# HITB_AMS_V1_3.net
KiCad netlist of a schematic drawn in EAGLE
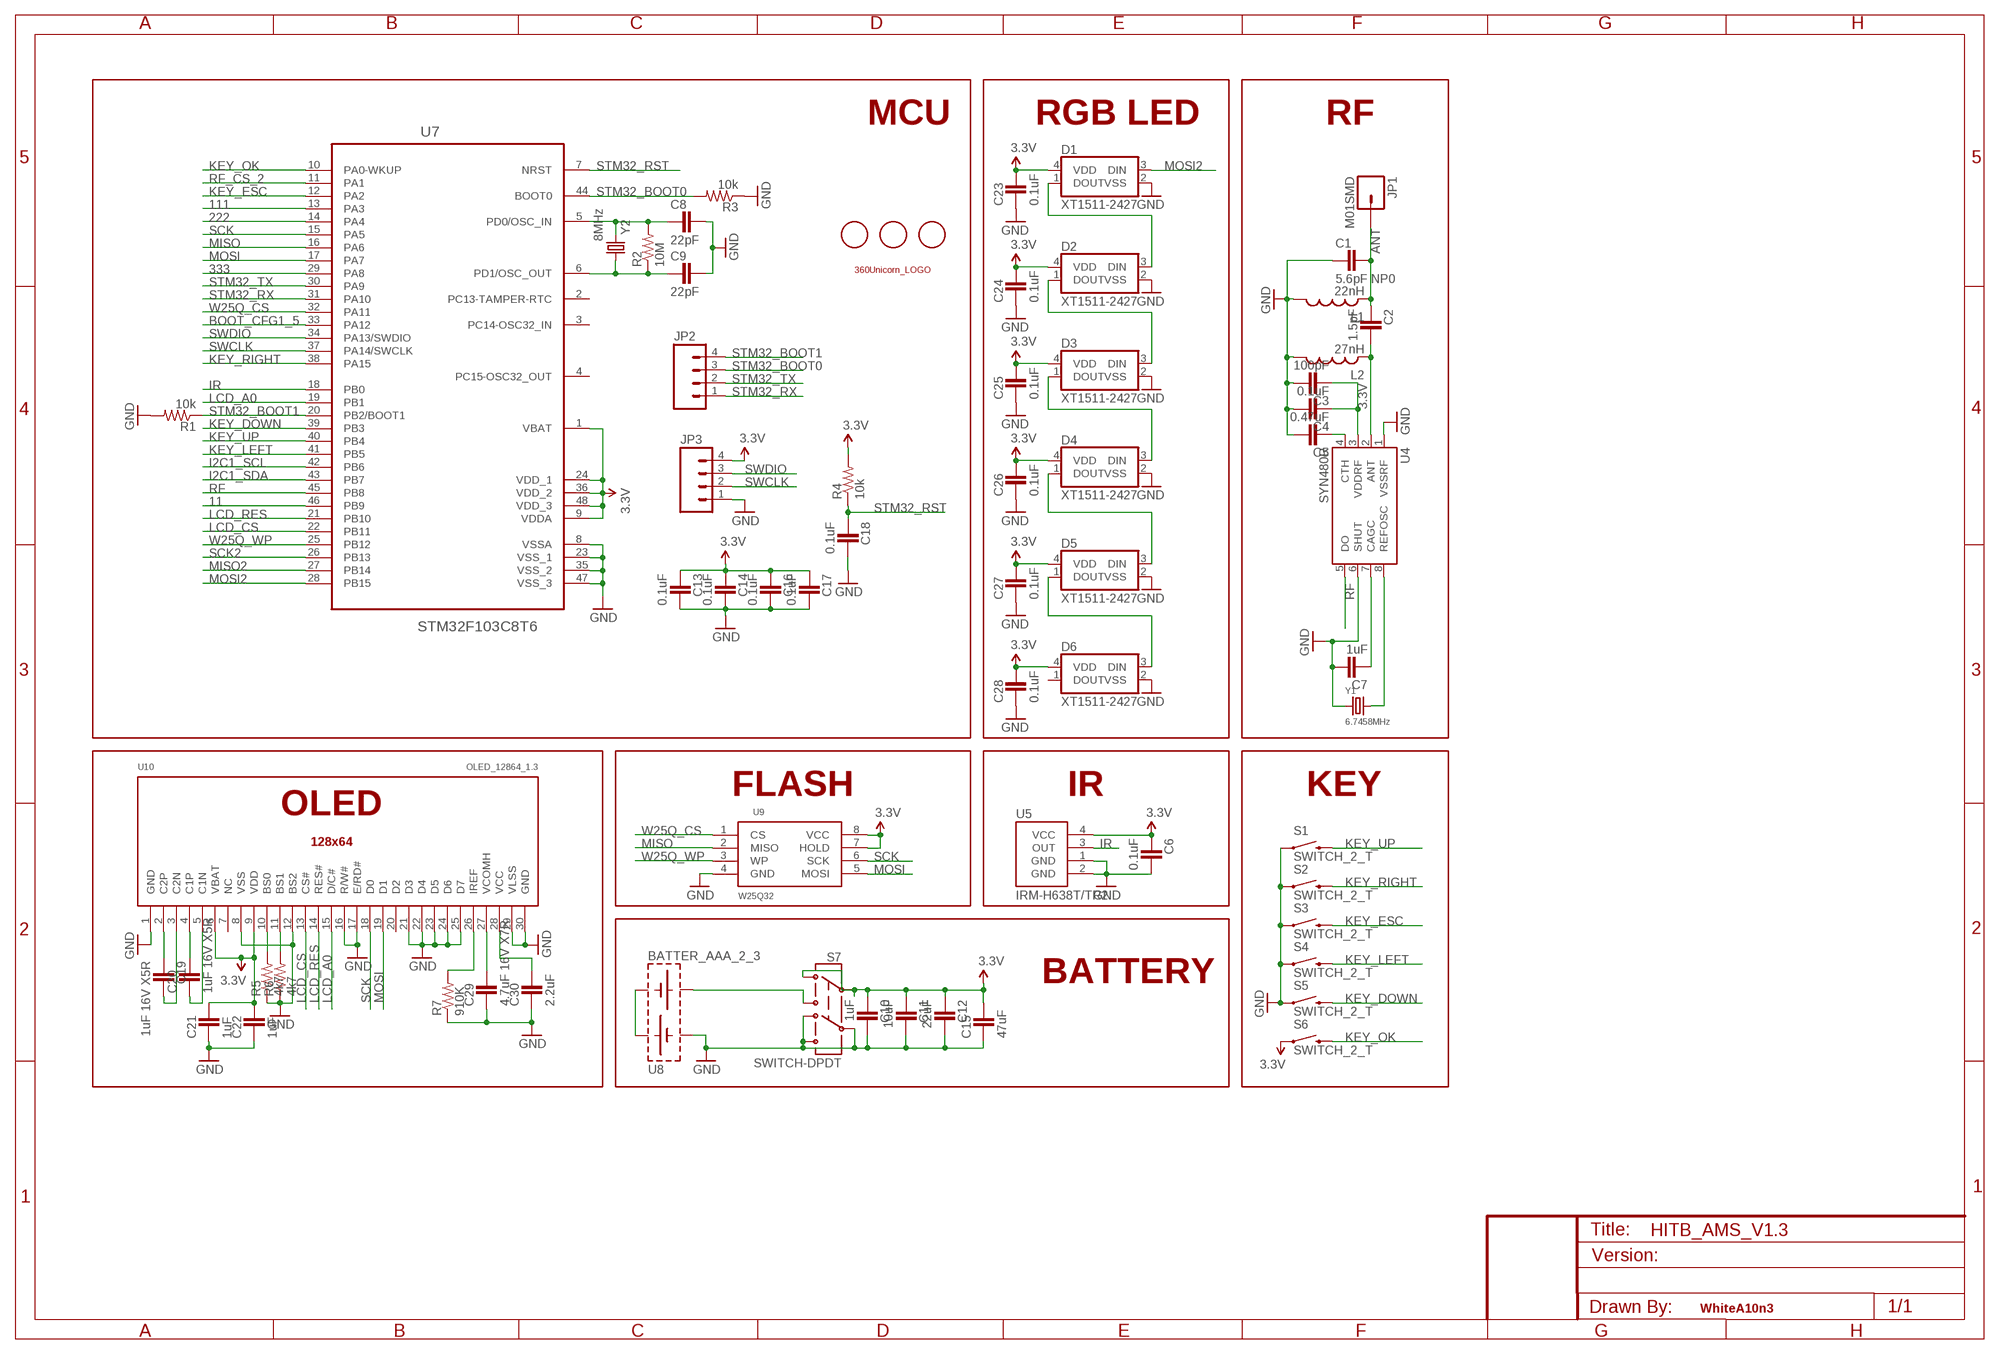
[diagram p0: schematic, sheet 1]

(export (version "E")
  (design (tool "Eeschema 10.0.6"))
  (components
    (comp (ref "C1")
      (value "5.6pF NP0")
      (footprint "eagle-import:0603-CAP")
      (libsource (lib "eagle-import") (part "CAP0603"))
    )
    (comp (ref "C2")
      (value "1.5pF")
      (footprint "eagle-import:0603-CAP")
      (libsource (lib "eagle-import") (part "CAP0603"))
    )
    (comp (ref "C3")
      (value "100pF")
      (footprint "eagle-import:0603-CAP")
      (libsource (lib "eagle-import") (part "CAP0603"))
    )
    (comp (ref "C4")
      (value "0.1uF")
      (footprint "eagle-import:0603-CAP")
      (libsource (lib "eagle-import") (part "CAP0603"))
    )
    (comp (ref "C5")
      (value "0.47uF")
      (footprint "eagle-import:0603-CAP")
      (libsource (lib "eagle-import") (part "CAP0603"))
    )
    (comp (ref "C6")
      (value "0.1uF")
      (footprint "eagle-import:0603-CAP")
      (libsource (lib "eagle-import") (part "CAP0603"))
    )
    (comp (ref "C7")
      (value "1uF")
      (footprint "eagle-import:0603-CAP")
      (libsource (lib "eagle-import") (part "CAP0603"))
    )
    (comp (ref "C8")
      (value "22pF")
      (footprint "eagle-import:0603-CAP")
      (libsource (lib "eagle-import") (part "CAP0603"))
    )
    (comp (ref "C9")
      (value "22pF")
      (footprint "eagle-import:0603-CAP")
      (libsource (lib "eagle-import") (part "CAP0603"))
    )
    (comp (ref "C10")
      (value "1uF")
      (footprint "eagle-import:0603-CAP")
      (libsource (lib "eagle-import") (part "CAP0603"))
    )
    (comp (ref "C11")
      (value "10uF")
      (footprint "eagle-import:0603-CAP")
      (libsource (lib "eagle-import") (part "CAP0603"))
    )
    (comp (ref "C12")
      (value "22uF")
      (footprint "eagle-import:0603-CAP")
      (libsource (lib "eagle-import") (part "CAP0603"))
    )
    (comp (ref "C13")
      (value "0.1uF")
      (footprint "eagle-import:0603-CAP")
      (libsource (lib "eagle-import") (part "CAP0603"))
    )
    (comp (ref "C14")
      (value "0.1uF")
      (footprint "eagle-import:0603-CAP")
      (libsource (lib "eagle-import") (part "CAP0603"))
    )
    (comp (ref "C15")
      (value "47uF")
      (footprint "eagle-import:1206")
      (libsource (lib "eagle-import") (part "CAP1206"))
    )
    (comp (ref "C16")
      (value "0.1uF")
      (footprint "eagle-import:0603-CAP")
      (libsource (lib "eagle-import") (part "CAP0603"))
    )
    (comp (ref "C17")
      (value "0.1uF")
      (footprint "eagle-import:0603-CAP")
      (libsource (lib "eagle-import") (part "CAP0603"))
    )
    (comp (ref "C18")
      (value "0.1uF")
      (footprint "eagle-import:0603-CAP")
      (libsource (lib "eagle-import") (part "CAP0603"))
    )
    (comp (ref "C19")
      (value "1uF 16V X5R")
      (footprint "eagle-import:0603-CAP")
      (libsource (lib "eagle-import") (part "CAP0603"))
    )
    (comp (ref "C20")
      (value "1uF 16V X5R")
      (footprint "eagle-import:0603-CAP")
      (libsource (lib "eagle-import") (part "CAP0603"))
    )
    (comp (ref "C21")
      (value "1uF")
      (footprint "eagle-import:0603-CAP")
      (libsource (lib "eagle-import") (part "CAP0603"))
    )
    (comp (ref "C22")
      (value "1uF")
      (footprint "eagle-import:0603-CAP")
      (libsource (lib "eagle-import") (part "CAP0603"))
    )
    (comp (ref "C23")
      (value "0.1uF")
      (footprint "eagle-import:0603-CAP")
      (libsource (lib "eagle-import") (part "CAP0603"))
    )
    (comp (ref "C24")
      (value "0.1uF")
      (footprint "eagle-import:0603-CAP")
      (libsource (lib "eagle-import") (part "CAP0603"))
    )
    (comp (ref "C25")
      (value "0.1uF")
      (footprint "eagle-import:0603-CAP")
      (libsource (lib "eagle-import") (part "CAP0603"))
    )
    (comp (ref "C26")
      (value "0.1uF")
      (footprint "eagle-import:0603-CAP")
      (libsource (lib "eagle-import") (part "CAP0603"))
    )
    (comp (ref "C27")
      (value "0.1uF")
      (footprint "eagle-import:0603-CAP")
      (libsource (lib "eagle-import") (part "CAP0603"))
    )
    (comp (ref "C28")
      (value "0.1uF")
      (footprint "eagle-import:0603-CAP")
      (libsource (lib "eagle-import") (part "CAP0603"))
    )
    (comp (ref "C29")
      (value "4.7uF 16V X7R")
      (footprint "eagle-import:0603-CAP")
      (libsource (lib "eagle-import") (part "CAP0603"))
    )
    (comp (ref "C30")
      (value "2.2uF")
      (footprint "eagle-import:0603-CAP")
      (libsource (lib "eagle-import") (part "CAP0603"))
    )
    (comp (ref "D1")
      (value "XT1511-2427")
      (footprint "eagle-import:RGB_2427")
      (libsource (lib "eagle-import") (part "XT1511-2427"))
    )
    (comp (ref "D2")
      (value "XT1511-2427")
      (footprint "eagle-import:RGB_2427")
      (libsource (lib "eagle-import") (part "XT1511-2427"))
    )
    (comp (ref "D3")
      (value "XT1511-2427")
      (footprint "eagle-import:RGB_2427")
      (libsource (lib "eagle-import") (part "XT1511-2427"))
    )
    (comp (ref "D4")
      (value "XT1511-2427")
      (footprint "eagle-import:RGB_2427")
      (libsource (lib "eagle-import") (part "XT1511-2427"))
    )
    (comp (ref "D5")
      (value "XT1511-2427")
      (footprint "eagle-import:RGB_2427")
      (libsource (lib "eagle-import") (part "XT1511-2427"))
    )
    (comp (ref "D6")
      (value "XT1511-2427")
      (footprint "eagle-import:RGB_2427")
      (libsource (lib "eagle-import") (part "XT1511-2427"))
    )
    (comp (ref "JP1")
      (value "M01SMD")
      (footprint "eagle-import:LUXEON-PAD")
      (libsource (lib "eagle-import") (part "M01SMD"))
    )
    (comp (ref "JP2")
      (value "M04_TEST_2")
      (footprint "eagle-import:1X04_TEST_2")
      (libsource (lib "eagle-import") (part "M04_TEST_2"))
    )
    (comp (ref "JP3")
      (value "M04_TEST_2")
      (footprint "eagle-import:1X04_TEST_2")
      (libsource (lib "eagle-import") (part "M04_TEST_2"))
    )
    (comp (ref "L1")
      (value "22nH")
      (footprint "eagle-import:0603")
      (libsource (lib "eagle-import") (part "INDUCTOR0603"))
    )
    (comp (ref "L2")
      (value "27nH")
      (footprint "eagle-import:0603")
      (libsource (lib "eagle-import") (part "INDUCTOR0603"))
    )
    (comp (ref "R1")
      (value "10k")
      (footprint "eagle-import:0603-RES")
      (libsource (lib "eagle-import") (part "RESISTOR0603-RES"))
    )
    (comp (ref "R2")
      (value "10M")
      (footprint "eagle-import:0603-RES")
      (libsource (lib "eagle-import") (part "RESISTOR0603-RES"))
    )
    (comp (ref "R3")
      (value "10k")
      (footprint "eagle-import:0603-RES")
      (libsource (lib "eagle-import") (part "RESISTOR0603-RES"))
    )
    (comp (ref "R4")
      (value "10k")
      (footprint "eagle-import:0603-RES")
      (libsource (lib "eagle-import") (part "RESISTOR0603-RES"))
    )
    (comp (ref "R5")
      (value "4k7")
      (footprint "eagle-import:0603-RES")
      (libsource (lib "eagle-import") (part "RESISTOR0603-RES"))
    )
    (comp (ref "R6")
      (value "4k7")
      (footprint "eagle-import:0603-RES")
      (libsource (lib "eagle-import") (part "RESISTOR0603-RES"))
    )
    (comp (ref "R7")
      (value "910K")
      (footprint "eagle-import:0603-RES")
      (libsource (lib "eagle-import") (part "RESISTOR0603-RES"))
    )
    (comp (ref "S1")
      (value "SWITCH_2_T")
      (footprint "eagle-import:BUTTON_TSSURX")
      (libsource (lib "eagle-import") (part "SWITCH_2_T"))
    )
    (comp (ref "S2")
      (value "SWITCH_2_T")
      (footprint "eagle-import:BUTTON_TSSURX")
      (libsource (lib "eagle-import") (part "SWITCH_2_T"))
    )
    (comp (ref "S3")
      (value "SWITCH_2_T")
      (footprint "eagle-import:BUTTON_TSSURX")
      (libsource (lib "eagle-import") (part "SWITCH_2_T"))
    )
    (comp (ref "S4")
      (value "SWITCH_2_T")
      (footprint "eagle-import:BUTTON_TSSURX")
      (libsource (lib "eagle-import") (part "SWITCH_2_T"))
    )
    (comp (ref "S5")
      (value "SWITCH_2_T")
      (footprint "eagle-import:BUTTON_TSSURX")
      (libsource (lib "eagle-import") (part "SWITCH_2_T"))
    )
    (comp (ref "S6")
      (value "SWITCH_2_T")
      (footprint "eagle-import:BUTTON_TSSURX")
      (libsource (lib "eagle-import") (part "SWITCH_2_T"))
    )
    (comp (ref "S7")
      (value "SWITCH-DPDT")
      (footprint "eagle-import:MSS22D18")
      (libsource (lib "eagle-import") (part "SWITCH-DPDT"))
    )
    (comp (ref "U1")
      (value "FIDUCIALMOUNT")
      (footprint "eagle-import:FIDUCIA-MOUNT")
      (libsource (lib "eagle-import") (part "FIDUCIALMOUNT"))
    )
    (comp (ref "U2")
      (value "FIDUCIALMOUNT")
      (footprint "eagle-import:FIDUCIA-MOUNT")
      (libsource (lib "eagle-import") (part "FIDUCIALMOUNT"))
    )
    (comp (ref "U3")
      (value "FIDUCIALMOUNT")
      (footprint "eagle-import:FIDUCIA-MOUNT")
      (libsource (lib "eagle-import") (part "FIDUCIALMOUNT"))
    )
    (comp (ref "U4")
      (value "SYN480R")
      (footprint "eagle-import:SO08")
      (libsource (lib "eagle-import") (part "SYN480R"))
    )
    (comp (ref "U5")
      (value "IRM-H638T/TR2")
      (footprint "eagle-import:IR_RECEIVE")
      (libsource (lib "eagle-import") (part "IR_RECIVE"))
    )
    (comp (ref "U6")
      (value "360UNICORN_LOGO_0.8_STOP")
      (footprint "eagle-import:360UNICORN_S0.8")
      (libsource (lib "eagle-import") (part "360UNICORN_LOGO_0.8_STOP"))
    )
    (comp (ref "U7")
      (value "STM32F103C8T6")
      (footprint "eagle-import:TQFP48")
      (libsource (lib "eagle-import") (part "STM32F103C8T6"))
    )
    (comp (ref "U8")
      (value "BATTER_AAA_2_3")
      (footprint "eagle-import:BATTER_AAA_3")
      (libsource (lib "eagle-import") (part "BATTER_AAA_2_3"))
    )
    (comp (ref "U9")
      (value "W25Q32")
      (footprint "eagle-import:SO08-EIAJ")
      (libsource (lib "eagle-import") (part "SPI_FLASH-X25XXSMD1"))
    )
    (comp (ref "U10")
      (value "OLED_12864_1.3")
      (footprint "eagle-import:OLED_12864_1.3")
      (libsource (lib "eagle-import") (part "OLED_12864_1.3"))
    )
    (comp (ref "Y1")
      (value "6.7458MHz")
      (footprint "eagle-import:HC49UP")
      (libsource (lib "eagle-import") (part "CRYSTALSMD"))
    )
    (comp (ref "Y2")
      (value "8MHz")
      (footprint "eagle-import:CRYSTAL-SMD-3225")
      (libsource (lib "eagle-import") (part "CRYSTAL_3225"))
    )
  )
  (nets
    (net (code "1") (name "/11") (class "Default")
      (node (ref "U7") (pin "46") (pinfunction "PB9_46") (pintype "bidirectional"))
    )
    (net (code "2") (name "/111") (class "Default")
      (node (ref "U7") (pin "13") (pinfunction "PA3_13") (pintype "bidirectional"))
    )
    (net (code "3") (name "/222") (class "Default")
      (node (ref "U7") (pin "14") (pinfunction "PA4_14") (pintype "bidirectional"))
    )
    (net (code "4") (name "/333") (class "Default")
      (node (ref "U7") (pin "29") (pinfunction "PA8_29") (pintype "bidirectional"))
    )
    (net (code "5") (name "/ANT") (class "Default")
      (node (ref "C1") (pin "1") (pinfunction "1_1") (pintype "passive"))
      (node (ref "C2") (pin "2") (pinfunction "2_2") (pintype "passive"))
      (node (ref "JP1") (pin "P$1") (pinfunction "1_P$1") (pintype "passive"))
      (node (ref "L1") (pin "1") (pinfunction "1_1") (pintype "passive"))
    )
    (net (code "6") (name "/BOOT_CFG1_5") (class "Default")
      (node (ref "U7") (pin "33") (pinfunction "PA12_33") (pintype "bidirectional"))
    )
    (net (code "7") (name "/I2C1_SCL") (class "Default")
      (node (ref "U7") (pin "42") (pinfunction "PB6_42") (pintype "bidirectional"))
    )
    (net (code "8") (name "/I2C1_SDA") (class "Default")
      (node (ref "U7") (pin "43") (pinfunction "PB7_43") (pintype "bidirectional"))
    )
    (net (code "9") (name "/IR") (class "Default")
      (node (ref "U5") (pin "3") (pinfunction "OUT_3") (pintype "bidirectional"))
      (node (ref "U7") (pin "18") (pinfunction "PB0_18") (pintype "bidirectional"))
    )
    (net (code "10") (name "/KEY_DOWN") (class "Default")
      (node (ref "S5") (pin "P$2") (pinfunction "2_P$2") (pintype "passive"))
      (node (ref "U7") (pin "39") (pinfunction "PB3_39") (pintype "bidirectional"))
    )
    (net (code "11") (name "/KEY_ESC") (class "Default")
      (node (ref "S3") (pin "P$2") (pinfunction "2_P$2") (pintype "passive"))
      (node (ref "U7") (pin "12") (pinfunction "PA2_12") (pintype "bidirectional"))
    )
    (net (code "12") (name "/KEY_LEFT") (class "Default")
      (node (ref "S4") (pin "P$2") (pinfunction "2_P$2") (pintype "passive"))
      (node (ref "U7") (pin "41") (pinfunction "PB5_41") (pintype "bidirectional"))
    )
    (net (code "13") (name "/KEY_OK") (class "Default")
      (node (ref "S6") (pin "P$2") (pinfunction "2_P$2") (pintype "passive"))
      (node (ref "U7") (pin "10") (pinfunction "PA0-WKUP_10") (pintype "bidirectional"))
    )
    (net (code "14") (name "/KEY_RIGHT") (class "Default")
      (node (ref "S2") (pin "P$2") (pinfunction "2_P$2") (pintype "passive"))
      (node (ref "U7") (pin "38") (pinfunction "PA15_38") (pintype "bidirectional"))
    )
    (net (code "15") (name "/KEY_UP") (class "Default")
      (node (ref "S1") (pin "P$2") (pinfunction "2_P$2") (pintype "passive"))
      (node (ref "U7") (pin "40") (pinfunction "PB4_40") (pintype "bidirectional"))
    )
    (net (code "16") (name "/LCD_A0") (class "Default")
      (node (ref "U10") (pin "15") (pinfunction "D/C#_15") (pintype "bidirectional"))
      (node (ref "U7") (pin "19") (pinfunction "PB1_19") (pintype "bidirectional"))
    )
    (net (code "17") (name "/LCD_CS") (class "Default")
      (node (ref "U10") (pin "13") (pinfunction "CS#_13") (pintype "bidirectional"))
      (node (ref "U7") (pin "22") (pinfunction "PB11_22") (pintype "bidirectional"))
    )
    (net (code "18") (name "/LCD_RES") (class "Default")
      (node (ref "U10") (pin "14") (pinfunction "RES#_14") (pintype "bidirectional"))
      (node (ref "U7") (pin "21") (pinfunction "PB10_21") (pintype "bidirectional"))
    )
    (net (code "19") (name "/MISO") (class "Default")
      (node (ref "U7") (pin "16") (pinfunction "PA6_16") (pintype "bidirectional"))
      (node (ref "U9") (pin "2") (pinfunction "MISO_2") (pintype "bidirectional"))
    )
    (net (code "20") (name "/MISO2") (class "Default")
      (node (ref "U7") (pin "27") (pinfunction "PB14_27") (pintype "bidirectional"))
    )
    (net (code "21") (name "/MOSI") (class "Default")
      (node (ref "U10") (pin "19") (pinfunction "D1_19") (pintype "bidirectional"))
      (node (ref "U7") (pin "17") (pinfunction "PA7_17") (pintype "bidirectional"))
      (node (ref "U9") (pin "5") (pinfunction "MOSI_5") (pintype "bidirectional"))
    )
    (net (code "22") (name "/MOSI2") (class "Default")
      (node (ref "D1") (pin "3") (pinfunction "DIN_3") (pintype "bidirectional"))
      (node (ref "U7") (pin "28") (pinfunction "PB15_28") (pintype "bidirectional"))
    )
    (net (code "23") (name "/RF") (class "Default")
      (node (ref "U4") (pin "5") (pinfunction "DO_5") (pintype "bidirectional"))
      (node (ref "U7") (pin "45") (pinfunction "PB8_45") (pintype "bidirectional"))
    )
    (net (code "24") (name "/RF_CS_2") (class "Default")
      (node (ref "U7") (pin "11") (pinfunction "PA1_11") (pintype "bidirectional"))
    )
    (net (code "25") (name "/SCK") (class "Default")
      (node (ref "U10") (pin "18") (pinfunction "D0_18") (pintype "bidirectional"))
      (node (ref "U7") (pin "15") (pinfunction "PA5_15") (pintype "bidirectional"))
      (node (ref "U9") (pin "6") (pinfunction "SCK_6") (pintype "bidirectional"))
    )
    (net (code "26") (name "/SCK2") (class "Default")
      (node (ref "U7") (pin "26") (pinfunction "PB13_26") (pintype "bidirectional"))
    )
    (net (code "27") (name "/STM32_BOOT0") (class "Default")
      (node (ref "JP2") (pin "3") (pinfunction "3_3") (pintype "passive"))
      (node (ref "R3") (pin "2") (pinfunction "2_2") (pintype "passive"))
      (node (ref "U7") (pin "44") (pinfunction "BOOT0_44") (pintype "input"))
    )
    (net (code "28") (name "/STM32_BOOT1") (class "Default")
      (node (ref "JP2") (pin "4") (pinfunction "4_4") (pintype "passive"))
      (node (ref "R1") (pin "1") (pinfunction "1_1") (pintype "passive"))
      (node (ref "U7") (pin "20") (pinfunction "PB2/BOOT1_20") (pintype "bidirectional"))
    )
    (net (code "29") (name "/STM32_RST") (class "Default")
      (node (ref "C18") (pin "2") (pinfunction "2_2") (pintype "passive"))
      (node (ref "R4") (pin "1") (pinfunction "1_1") (pintype "passive"))
      (node (ref "U7") (pin "7") (pinfunction "NRST_7") (pintype "bidirectional"))
    )
    (net (code "30") (name "/STM32_RX") (class "Default")
      (node (ref "JP2") (pin "1") (pinfunction "1_1") (pintype "passive"))
      (node (ref "U7") (pin "31") (pinfunction "PA10_31") (pintype "bidirectional"))
    )
    (net (code "31") (name "/STM32_TX") (class "Default")
      (node (ref "JP2") (pin "2") (pinfunction "2_2") (pintype "passive"))
      (node (ref "U7") (pin "30") (pinfunction "PA9_30") (pintype "bidirectional"))
    )
    (net (code "32") (name "/SWCLK") (class "Default")
      (node (ref "JP3") (pin "2") (pinfunction "2_2") (pintype "passive"))
      (node (ref "U7") (pin "37") (pinfunction "PA14/SWCLK_37") (pintype "bidirectional"))
    )
    (net (code "33") (name "/SWDIO") (class "Default")
      (node (ref "JP3") (pin "3") (pinfunction "3_3") (pintype "passive"))
      (node (ref "U7") (pin "34") (pinfunction "PA13/SWDIO_34") (pintype "bidirectional"))
    )
    (net (code "34") (name "/W25Q_CS") (class "Default")
      (node (ref "U7") (pin "32") (pinfunction "PA11_32") (pintype "bidirectional"))
      (node (ref "U9") (pin "1") (pinfunction "CS_1") (pintype "bidirectional"))
    )
    (net (code "35") (name "/W25Q_WP") (class "Default")
      (node (ref "U7") (pin "25") (pinfunction "PB12_25") (pintype "bidirectional"))
      (node (ref "U9") (pin "3") (pinfunction "WP_3") (pintype "bidirectional"))
    )
    (net (code "36") (name "3.3V") (class "Default")
      (node (ref "C10") (pin "2") (pinfunction "2_2") (pintype "passive"))
      (node (ref "C11") (pin "2") (pinfunction "2_2") (pintype "passive"))
      (node (ref "C12") (pin "2") (pinfunction "2_2") (pintype "passive"))
      (node (ref "C13") (pin "2") (pinfunction "2_2") (pintype "passive"))
      (node (ref "C14") (pin "2") (pinfunction "2_2") (pintype "passive"))
      (node (ref "C15") (pin "1") (pinfunction "1_1") (pintype "passive"))
      (node (ref "C16") (pin "2") (pinfunction "2_2") (pintype "passive"))
      (node (ref "C17") (pin "2") (pinfunction "2_2") (pintype "passive"))
      (node (ref "C21") (pin "1") (pinfunction "1_1") (pintype "passive"))
      (node (ref "C22") (pin "1") (pinfunction "1_1") (pintype "passive"))
      (node (ref "C23") (pin "1") (pinfunction "1_1") (pintype "passive"))
      (node (ref "C24") (pin "1") (pinfunction "1_1") (pintype "passive"))
      (node (ref "C25") (pin "1") (pinfunction "1_1") (pintype "passive"))
      (node (ref "C26") (pin "1") (pinfunction "1_1") (pintype "passive"))
      (node (ref "C27") (pin "1") (pinfunction "1_1") (pintype "passive"))
      (node (ref "C28") (pin "1") (pinfunction "1_1") (pintype "passive"))
      (node (ref "C3") (pin "2") (pinfunction "2_2") (pintype "passive"))
      (node (ref "C4") (pin "2") (pinfunction "2_2") (pintype "passive"))
      (node (ref "C6") (pin "2") (pinfunction "2_2") (pintype "passive"))
      (node (ref "D1") (pin "4") (pinfunction "VDD_4") (pintype "power_in"))
      (node (ref "D2") (pin "4") (pinfunction "VDD_4") (pintype "power_in"))
      (node (ref "D3") (pin "4") (pinfunction "VDD_4") (pintype "power_in"))
      (node (ref "D4") (pin "4") (pinfunction "VDD_4") (pintype "power_in"))
      (node (ref "D5") (pin "4") (pinfunction "VDD_4") (pintype "power_in"))
      (node (ref "D6") (pin "4") (pinfunction "VDD_4") (pintype "power_in"))
      (node (ref "JP3") (pin "4") (pinfunction "4_4") (pintype "passive"))
      (node (ref "R4") (pin "2") (pinfunction "2_2") (pintype "passive"))
      (node (ref "S6") (pin "P$1") (pinfunction "1_P$1") (pintype "passive"))
      (node (ref "S7") (pin "1") (pinfunction "1_1") (pintype "bidirectional"))
      (node (ref "S7") (pin "2") (pinfunction "2_2") (pintype "bidirectional"))
      (node (ref "U10") (pin "6") (pinfunction "VBAT_6") (pintype "bidirectional"))
      (node (ref "U10") (pin "9") (pinfunction "VDD_9") (pintype "power_in"))
      (node (ref "U4") (pin "3") (pinfunction "VDDRF_3") (pintype "power_in"))
      (node (ref "U5") (pin "4") (pinfunction "VCC_4") (pintype "bidirectional"))
      (node (ref "U7") (pin "1") (pinfunction "VBAT_1") (pintype "power_in"))
      (node (ref "U7") (pin "24") (pinfunction "VDD_1_24") (pintype "power_in"))
      (node (ref "U7") (pin "36") (pinfunction "VDD_2_36") (pintype "power_in"))
      (node (ref "U7") (pin "48") (pinfunction "VDD_3_48") (pintype "power_in"))
      (node (ref "U7") (pin "9") (pinfunction "VDDA_9") (pintype "power_in"))
      (node (ref "U9") (pin "7") (pinfunction "HOLD_7") (pintype "bidirectional"))
      (node (ref "U9") (pin "8") (pinfunction "VCC_8") (pintype "bidirectional"))
    )
    (net (code "37") (name "GND") (class "Default")
      (node (ref "C1") (pin "2") (pinfunction "2_2") (pintype "passive"))
      (node (ref "C10") (pin "1") (pinfunction "1_1") (pintype "passive"))
      (node (ref "C11") (pin "1") (pinfunction "1_1") (pintype "passive"))
      (node (ref "C12") (pin "1") (pinfunction "1_1") (pintype "passive"))
      (node (ref "C13") (pin "1") (pinfunction "1_1") (pintype "passive"))
      (node (ref "C14") (pin "1") (pinfunction "1_1") (pintype "passive"))
      (node (ref "C15") (pin "2") (pinfunction "2_2") (pintype "passive"))
      (node (ref "C16") (pin "1") (pinfunction "1_1") (pintype "passive"))
      (node (ref "C17") (pin "1") (pinfunction "1_1") (pintype "passive"))
      (node (ref "C18") (pin "1") (pinfunction "1_1") (pintype "passive"))
      (node (ref "C21") (pin "2") (pinfunction "2_2") (pintype "passive"))
      (node (ref "C22") (pin "2") (pinfunction "2_2") (pintype "passive"))
      (node (ref "C23") (pin "2") (pinfunction "2_2") (pintype "passive"))
      (node (ref "C24") (pin "2") (pinfunction "2_2") (pintype "passive"))
      (node (ref "C25") (pin "2") (pinfunction "2_2") (pintype "passive"))
      (node (ref "C26") (pin "2") (pinfunction "2_2") (pintype "passive"))
      (node (ref "C27") (pin "2") (pinfunction "2_2") (pintype "passive"))
      (node (ref "C28") (pin "2") (pinfunction "2_2") (pintype "passive"))
      (node (ref "C29") (pin "2") (pinfunction "2_2") (pintype "passive"))
      (node (ref "C3") (pin "1") (pinfunction "1_1") (pintype "passive"))
      (node (ref "C30") (pin "2") (pinfunction "2_2") (pintype "passive"))
      (node (ref "C4") (pin "1") (pinfunction "1_1") (pintype "passive"))
      (node (ref "C5") (pin "1") (pinfunction "1_1") (pintype "passive"))
      (node (ref "C6") (pin "1") (pinfunction "1_1") (pintype "passive"))
      (node (ref "C7") (pin "1") (pinfunction "1_1") (pintype "passive"))
      (node (ref "C8") (pin "1") (pinfunction "1_1") (pintype "passive"))
      (node (ref "C9") (pin "1") (pinfunction "1_1") (pintype "passive"))
      (node (ref "D1") (pin "2") (pinfunction "VSS_2") (pintype "power_in"))
      (node (ref "D2") (pin "2") (pinfunction "VSS_2") (pintype "power_in"))
      (node (ref "D3") (pin "2") (pinfunction "VSS_2") (pintype "power_in"))
      (node (ref "D4") (pin "2") (pinfunction "VSS_2") (pintype "power_in"))
      (node (ref "D5") (pin "2") (pinfunction "VSS_2") (pintype "power_in"))
      (node (ref "D6") (pin "2") (pinfunction "VSS_2") (pintype "power_in"))
      (node (ref "JP3") (pin "1") (pinfunction "1_1") (pintype "passive"))
      (node (ref "L1") (pin "2") (pinfunction "2_2") (pintype "passive"))
      (node (ref "L2") (pin "2") (pinfunction "2_2") (pintype "passive"))
      (node (ref "R1") (pin "2") (pinfunction "2_2") (pintype "passive"))
      (node (ref "R3") (pin "1") (pinfunction "1_1") (pintype "passive"))
      (node (ref "R5") (pin "1") (pinfunction "1_1") (pintype "passive"))
      (node (ref "R6") (pin "1") (pinfunction "1_1") (pintype "passive"))
      (node (ref "R7") (pin "1") (pinfunction "1_1") (pintype "passive"))
      (node (ref "S1") (pin "P$1") (pinfunction "1_P$1") (pintype "passive"))
      (node (ref "S2") (pin "P$1") (pinfunction "1_P$1") (pintype "passive"))
      (node (ref "S3") (pin "P$1") (pinfunction "1_P$1") (pintype "passive"))
      (node (ref "S4") (pin "P$1") (pinfunction "1_P$1") (pintype "passive"))
      (node (ref "S5") (pin "P$1") (pinfunction "1_P$1") (pintype "passive"))
      (node (ref "S7") (pin "4") (pinfunction "4_4") (pintype "bidirectional"))
      (node (ref "S7") (pin "5") (pinfunction "5_5") (pintype "bidirectional"))
      (node (ref "S7") (pin "6") (pinfunction "6_6") (pintype "bidirectional"))
      (node (ref "U10") (pin "1") (pinfunction "GND_1") (pintype "power_in"))
      (node (ref "U10") (pin "12") (pinfunction "BS2_12") (pintype "bidirectional"))
      (node (ref "U10") (pin "16") (pinfunction "R/W#_16") (pintype "bidirectional"))
      (node (ref "U10") (pin "17") (pinfunction "E/RD#_17") (pintype "bidirectional"))
      (node (ref "U10") (pin "21") (pinfunction "D3_21") (pintype "bidirectional"))
      (node (ref "U10") (pin "22") (pinfunction "D4_22") (pintype "bidirectional"))
      (node (ref "U10") (pin "23") (pinfunction "D5_23") (pintype "bidirectional"))
      (node (ref "U10") (pin "24") (pinfunction "D6_24") (pintype "bidirectional"))
      (node (ref "U10") (pin "25") (pinfunction "D7_25") (pintype "bidirectional"))
      (node (ref "U10") (pin "29") (pinfunction "VLSS_29") (pintype "power_in"))
      (node (ref "U10") (pin "30") (pinfunction "GND_30") (pintype "power_in"))
      (node (ref "U10") (pin "8") (pinfunction "VSS_8") (pintype "power_in"))
      (node (ref "U4") (pin "1") (pinfunction "VSSRF_1") (pintype "power_in"))
      (node (ref "U4") (pin "6") (pinfunction "SHUT_6") (pintype "bidirectional"))
      (node (ref "U5") (pin "1") (pinfunction "GND_1") (pintype "bidirectional"))
      (node (ref "U5") (pin "2") (pinfunction "GND_2") (pintype "bidirectional"))
      (node (ref "U7") (pin "23") (pinfunction "VSS_1_23") (pintype "power_in"))
      (node (ref "U7") (pin "35") (pinfunction "VSS_2_35") (pintype "power_in"))
      (node (ref "U7") (pin "47") (pinfunction "VSS_3_47") (pintype "power_in"))
      (node (ref "U7") (pin "8") (pinfunction "VSSA_8") (pintype "power_in"))
      (node (ref "U8") (pin "A-") (pinfunction "A-_A-") (pintype "power_in"))
      (node (ref "U9") (pin "4") (pinfunction "GND_4") (pintype "bidirectional"))
      (node (ref "Y1") (pin "1") (pinfunction "1_1") (pintype "passive"))
    )
    (net (code "38") (name "Net-(D1-DOUT)") (class "Default")
      (node (ref "D1") (pin "1") (pinfunction "DOUT_1") (pintype "bidirectional"))
      (node (ref "D2") (pin "3") (pinfunction "DIN_3") (pintype "bidirectional"))
    )
    (net (code "39") (name "Net-(D2-DOUT)") (class "Default")
      (node (ref "D2") (pin "1") (pinfunction "DOUT_1") (pintype "bidirectional"))
      (node (ref "D3") (pin "3") (pinfunction "DIN_3") (pintype "bidirectional"))
    )
    (net (code "40") (name "Net-(D3-DOUT)") (class "Default")
      (node (ref "D3") (pin "1") (pinfunction "DOUT_1") (pintype "bidirectional"))
      (node (ref "D4") (pin "3") (pinfunction "DIN_3") (pintype "bidirectional"))
    )
    (net (code "41") (name "Net-(D4-DOUT)") (class "Default")
      (node (ref "D4") (pin "1") (pinfunction "DOUT_1") (pintype "bidirectional"))
      (node (ref "D5") (pin "3") (pinfunction "DIN_3") (pintype "bidirectional"))
    )
    (net (code "42") (name "Net-(D5-DOUT)") (class "Default")
      (node (ref "D5") (pin "1") (pinfunction "DOUT_1") (pintype "bidirectional"))
      (node (ref "D6") (pin "3") (pinfunction "DIN_3") (pintype "bidirectional"))
    )
    (net (code "43") (name "Net-(S7-Pad3)") (class "Default")
      (node (ref "S7") (pin "3") (pinfunction "3_3") (pintype "bidirectional"))
      (node (ref "U8") (pin "B+") (pinfunction "B+_B+") (pintype "power_in"))
    )
    (net (code "44") (name "Net-(U4-ANT)") (class "Default")
      (node (ref "C2") (pin "1") (pinfunction "1_1") (pintype "passive"))
      (node (ref "L2") (pin "1") (pinfunction "1_1") (pintype "passive"))
      (node (ref "U4") (pin "2") (pinfunction "ANT_2") (pintype "bidirectional"))
    )
    (net (code "45") (name "Net-(U4-CAGC)") (class "Default")
      (node (ref "C7") (pin "2") (pinfunction "2_2") (pintype "passive"))
      (node (ref "U4") (pin "7") (pinfunction "CAGC_7") (pintype "bidirectional"))
    )
    (net (code "46") (name "Net-(U4-CTH)") (class "Default")
      (node (ref "C5") (pin "2") (pinfunction "2_2") (pintype "passive"))
      (node (ref "U4") (pin "4") (pinfunction "CTH_4") (pintype "bidirectional"))
    )
    (net (code "47") (name "Net-(U4-REFOSC)") (class "Default")
      (node (ref "U4") (pin "8") (pinfunction "REFOSC_8") (pintype "bidirectional"))
      (node (ref "Y1") (pin "2") (pinfunction "2_2") (pintype "passive"))
    )
    (net (code "48") (name "Net-(U7-PD0{slash}OSC_IN)") (class "Default")
      (node (ref "C8") (pin "2") (pinfunction "2_2") (pintype "passive"))
      (node (ref "R2") (pin "2") (pinfunction "2_2") (pintype "passive"))
      (node (ref "U7") (pin "5") (pinfunction "PD0/OSC_IN_5") (pintype "bidirectional"))
      (node (ref "Y2") (pin "1") (pinfunction "1_1") (pintype "passive"))
    )
    (net (code "49") (name "Net-(U7-PD1{slash}OSC_OUT)") (class "Default")
      (node (ref "C9") (pin "2") (pinfunction "2_2") (pintype "passive"))
      (node (ref "R2") (pin "1") (pinfunction "1_1") (pintype "passive"))
      (node (ref "U7") (pin "6") (pinfunction "PD1/OSC_OUT_6") (pintype "bidirectional"))
      (node (ref "Y2") (pin "3") (pinfunction "2_3") (pintype "passive"))
    )
    (net (code "50") (name "Net-(U8-PadA+)") (class "Default")
      (node (ref "U8") (pin "A+") (pinfunction "A+_A+") (pintype "power_in"))
      (node (ref "U8") (pin "B-") (pinfunction "B-_B-") (pintype "power_in"))
    )
    (net (code "51") (name "Net-(U10-BS0)") (class "Default")
      (node (ref "R5") (pin "2") (pinfunction "2_2") (pintype "passive"))
      (node (ref "U10") (pin "10") (pinfunction "BS0_10") (pintype "bidirectional"))
    )
    (net (code "52") (name "Net-(U10-BS1)") (class "Default")
      (node (ref "R6") (pin "2") (pinfunction "2_2") (pintype "passive"))
      (node (ref "U10") (pin "11") (pinfunction "BS1_11") (pintype "bidirectional"))
    )
    (net (code "53") (name "Net-(U10-C1N)") (class "Default")
      (node (ref "C20") (pin "2") (pinfunction "2_2") (pintype "passive"))
      (node (ref "U10") (pin "5") (pinfunction "C1N_5") (pintype "bidirectional"))
    )
    (net (code "54") (name "Net-(U10-C1P)") (class "Default")
      (node (ref "C20") (pin "1") (pinfunction "1_1") (pintype "passive"))
      (node (ref "U10") (pin "4") (pinfunction "C1P_4") (pintype "bidirectional"))
    )
    (net (code "55") (name "Net-(U10-C2N)") (class "Default")
      (node (ref "C19") (pin "1") (pinfunction "1_1") (pintype "passive"))
      (node (ref "U10") (pin "3") (pinfunction "C2N_3") (pintype "bidirectional"))
    )
    (net (code "56") (name "Net-(U10-C2P)") (class "Default")
      (node (ref "C19") (pin "2") (pinfunction "2_2") (pintype "passive"))
      (node (ref "U10") (pin "2") (pinfunction "C2P_2") (pintype "bidirectional"))
    )
    (net (code "57") (name "Net-(U10-IREF)") (class "Default")
      (node (ref "R7") (pin "2") (pinfunction "2_2") (pintype "passive"))
      (node (ref "U10") (pin "26") (pinfunction "IREF_26") (pintype "bidirectional"))
    )
    (net (code "58") (name "Net-(U10-VCC)") (class "Default")
      (node (ref "C30") (pin "1") (pinfunction "1_1") (pintype "passive"))
      (node (ref "U10") (pin "28") (pinfunction "VCC_28") (pintype "power_in"))
    )
    (net (code "59") (name "Net-(U10-VCOMH)") (class "Default")
      (node (ref "C29") (pin "1") (pinfunction "1_1") (pintype "passive"))
      (node (ref "U10") (pin "27") (pinfunction "VCOMH_27") (pintype "bidirectional"))
    )
    (net (code "60") (name "unconnected-(D6-DOUT-Pad1)") (class "Default")
      (node (ref "D6") (pin "1") (pinfunction "DOUT_1") (pintype "bidirectional"))
    )
    (net (code "61") (name "unconnected-(U7-PC13-TAMPER-RTC-Pad2)") (class "Default")
      (node (ref "U7") (pin "2") (pinfunction "PC13-TAMPER-RTC_2") (pintype "bidirectional"))
    )
    (net (code "62") (name "unconnected-(U7-PC14-OSC32_IN-Pad3)") (class "Default")
      (node (ref "U7") (pin "3") (pinfunction "PC14-OSC32_IN_3") (pintype "bidirectional"))
    )
    (net (code "63") (name "unconnected-(U7-PC15-OSC32_OUT-Pad4)") (class "Default")
      (node (ref "U7") (pin "4") (pinfunction "PC15-OSC32_OUT_4") (pintype "bidirectional"))
    )
    (net (code "64") (name "unconnected-(U10-D2-Pad20)") (class "Default")
      (node (ref "U10") (pin "20") (pinfunction "D2_20") (pintype "bidirectional"))
    )
    (net (code "65") (name "unconnected-(U10-NC-Pad7)") (class "Default")
      (node (ref "U10") (pin "7") (pinfunction "NC_7") (pintype "bidirectional"))
    )
  )
)
